# mcp1700_breakout.net
KiCad netlist of a schematic drawn in EAGLE
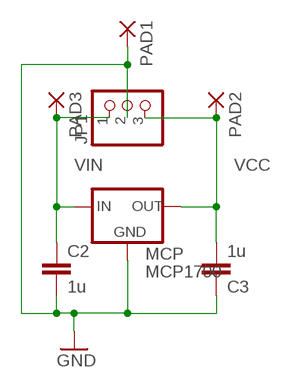
[diagram p0: schematic, sheet 1]

(export (version "E")
  (design (tool "Eeschema 10.0.6"))
  (components
    (comp (ref "C2")
      (value "1u")
      (footprint "eagle-import:C0805")
      (libsource (lib "eagle-import") (part "C-EUC0805"))
    )
    (comp (ref "C3")
      (value "1u")
      (footprint "eagle-import:C0805")
      (libsource (lib "eagle-import") (part "C-EUC0805"))
    )
    (comp (ref "JP1")
      (value "PINHD-1X3")
      (footprint "eagle-import:1X03")
      (libsource (lib "eagle-import") (part "PINHD-1X3"))
    )
    (comp (ref "MCP")
      (value "MCP1700")
      (footprint "eagle-import:SOT-23")
      (libsource (lib "eagle-import") (part "MCP1700SOT-23"))
    )
    (comp (ref "PAD1")
      (value "SMD2")
      (footprint "eagle-import:SMD1,27-2,54")
      (libsource (lib "eagle-import") (part "SMD2"))
    )
    (comp (ref "PAD2")
      (value "SMD2")
      (footprint "eagle-import:SMD1,27-2,54")
      (libsource (lib "eagle-import") (part "SMD2"))
    )
    (comp (ref "PAD3")
      (value "SMD2")
      (footprint "eagle-import:SMD1,27-2,54")
      (libsource (lib "eagle-import") (part "SMD2"))
    )
  )
  (nets
    (net (code "1") (name "/VCC") (class "Default")
      (node (ref "C3") (pin "2") (pinfunction "2_2") (pintype "passive"))
      (node (ref "JP1") (pin "3") (pinfunction "3_3") (pintype "passive"))
      (node (ref "MCP") (pin "2") (pinfunction "OUT_2") (pintype "passive"))
      (node (ref "PAD2") (pin "1") (pinfunction "P_1") (pintype "passive"))
    )
    (net (code "2") (name "/VIN") (class "Default")
      (node (ref "C2") (pin "1") (pinfunction "1_1") (pintype "passive"))
      (node (ref "JP1") (pin "1") (pinfunction "1_1") (pintype "passive"))
      (node (ref "MCP") (pin "3") (pinfunction "IN_3") (pintype "input"))
      (node (ref "PAD3") (pin "1") (pinfunction "P_1") (pintype "passive"))
    )
    (net (code "3") (name "GND") (class "Default")
      (node (ref "C2") (pin "2") (pinfunction "2_2") (pintype "passive"))
      (node (ref "C3") (pin "1") (pinfunction "1_1") (pintype "passive"))
      (node (ref "JP1") (pin "2") (pinfunction "2_2") (pintype "passive"))
      (node (ref "MCP") (pin "1") (pinfunction "GND_1") (pintype "input"))
      (node (ref "PAD1") (pin "1") (pinfunction "P_1") (pintype "passive"))
    )
  )
)
